# OpenBook_schematic.net
KiCad netlist of a schematic drawn in EAGLE
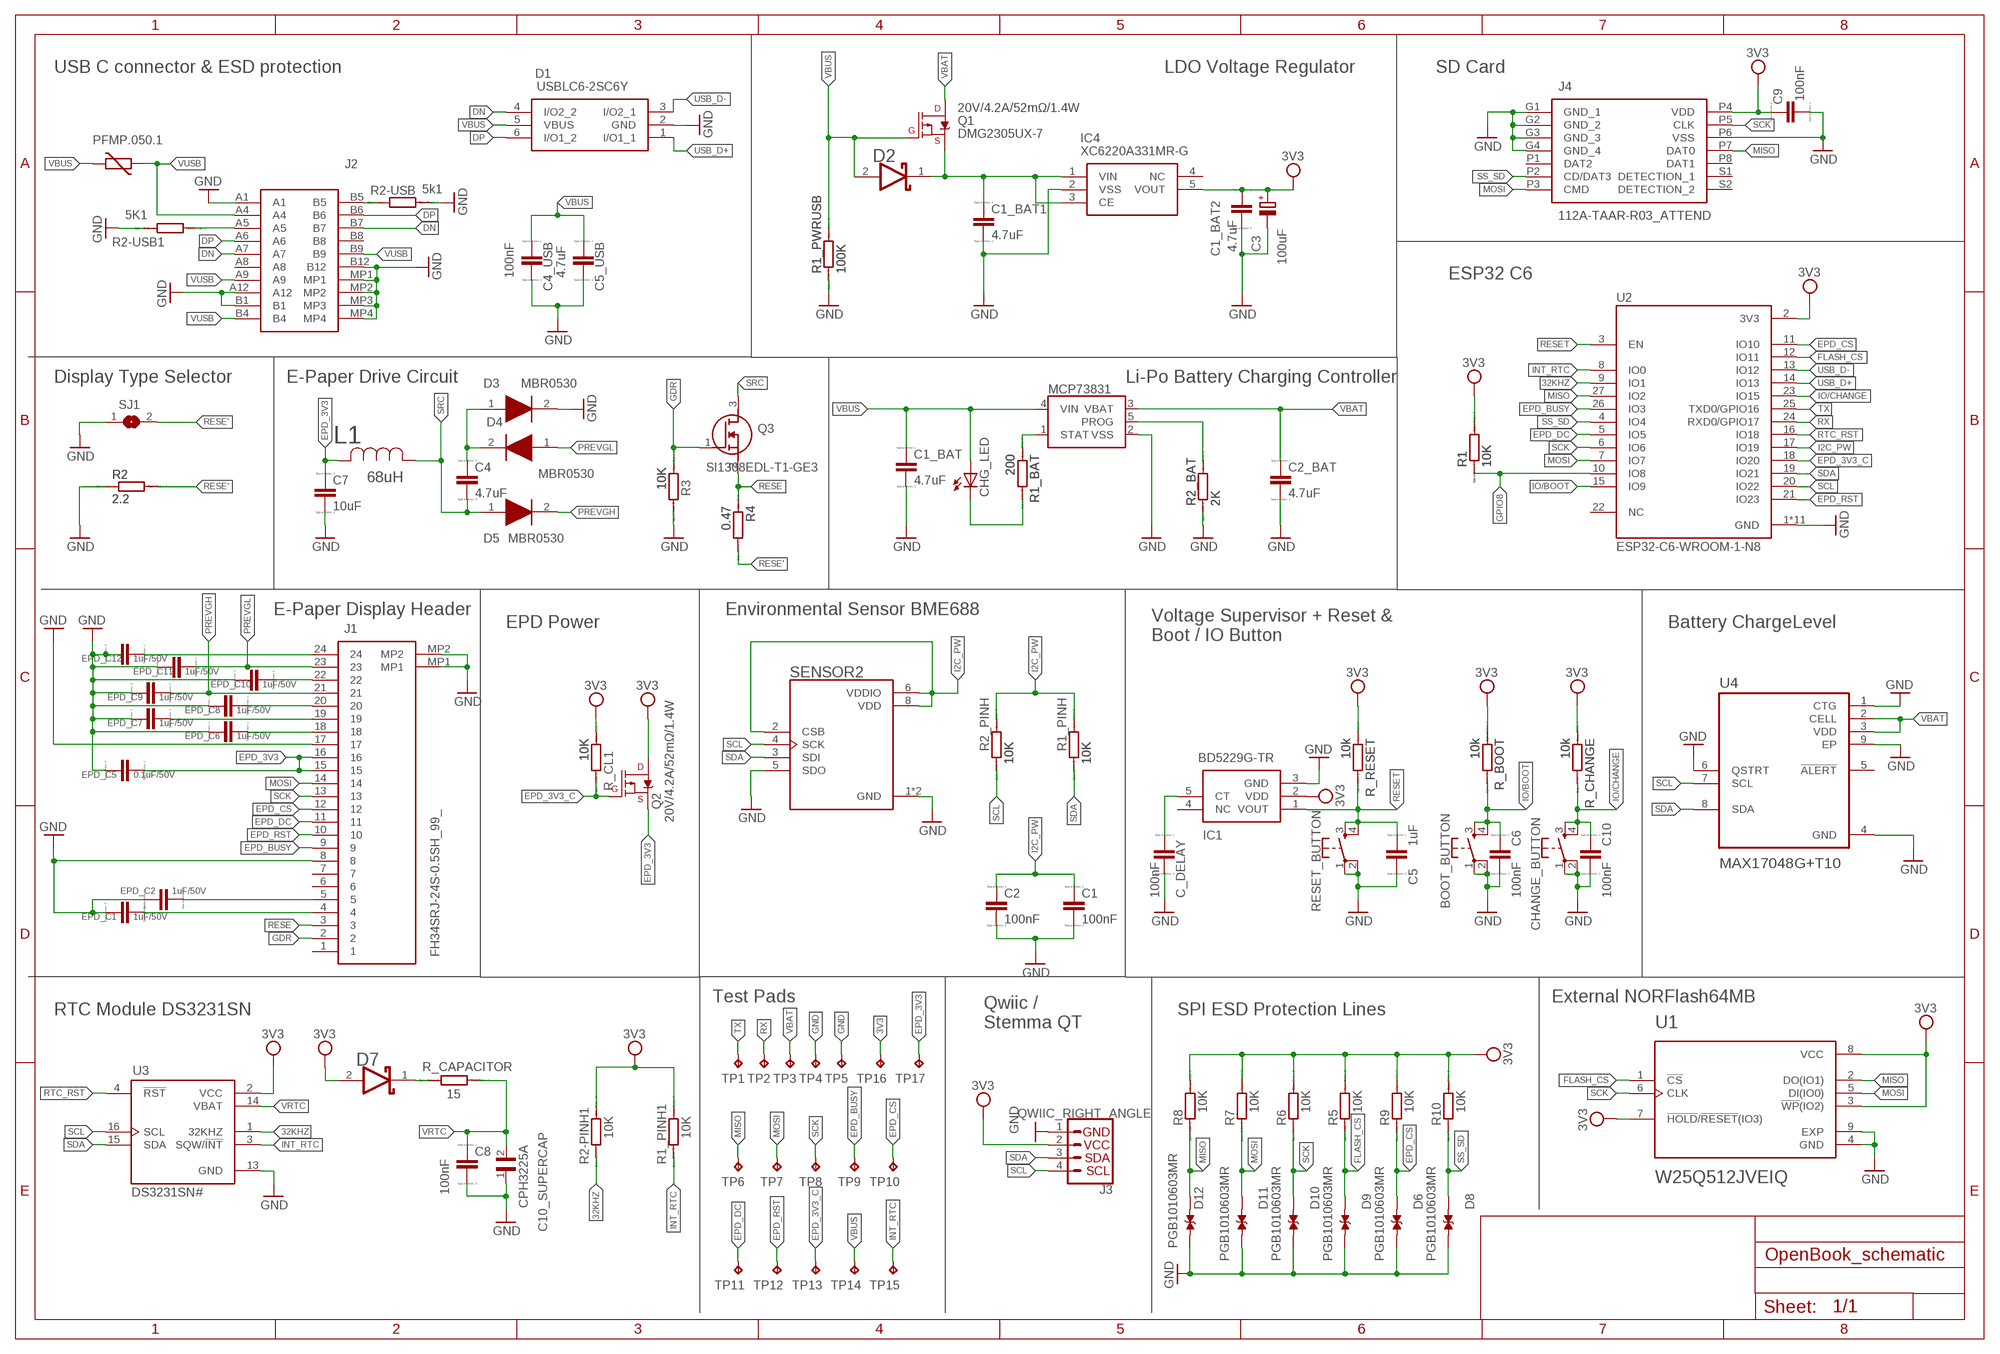
[diagram p0: schematic, sheet 1]

(export (version "E")
  (design (tool "Eeschema 10.0.6"))
  (components
    (comp (ref "BOOT_BUTTON")
      (value "BUTTON_CUSYOMV1")
      (footprint "eagle-import:MYBUTTON")
      (libsource (lib "eagle-import") (part "BUTTON_CUSYOMV1"))
    )
    (comp (ref "C1")
      (value "100nF")
      (footprint "eagle-import:EAGLE-LTSPICE_C0402")
      (libsource (lib "eagle-import") (part "EAGLE-LTSPICE_CC0402"))
    )
    (comp (ref "C1_BAT")
      (value "4.7uF")
      (footprint "eagle-import:EAGLE-LTSPICE_C0402")
      (libsource (lib "eagle-import") (part "EAGLE-LTSPICE_CC0402"))
    )
    (comp (ref "C1_BAT1")
      (value "4.7uF")
      (footprint "eagle-import:EAGLE-LTSPICE_C0402")
      (libsource (lib "eagle-import") (part "EAGLE-LTSPICE_CC0402"))
    )
    (comp (ref "C1_BAT2")
      (value "4.7uF")
      (footprint "eagle-import:EAGLE-LTSPICE_C0402")
      (libsource (lib "eagle-import") (part "EAGLE-LTSPICE_CC0402"))
    )
    (comp (ref "C2")
      (value "100nF")
      (footprint "eagle-import:EAGLE-LTSPICE_C0402")
      (libsource (lib "eagle-import") (part "EAGLE-LTSPICE_CC0402"))
    )
    (comp (ref "C2_BAT")
      (value "4.7uF")
      (footprint "eagle-import:EAGLE-LTSPICE_C0402")
      (libsource (lib "eagle-import") (part "EAGLE-LTSPICE_CC0402"))
    )
    (comp (ref "C3")
      (value "100uF")
      (footprint "eagle-import:RCL_CT3528")
      (libsource (lib "eagle-import") (part "RCL_CPOL-EUCT3528"))
    )
    (comp (ref "C4")
      (value "4.7uF")
      (footprint "eagle-import:EAGLE-LTSPICE_C0402")
      (libsource (lib "eagle-import") (part "EAGLE-LTSPICE_CC0402"))
    )
    (comp (ref "C4_USB")
      (value "100nF")
      (footprint "eagle-import:EAGLE-LTSPICE_C0402")
      (libsource (lib "eagle-import") (part "EAGLE-LTSPICE_CC0402"))
    )
    (comp (ref "C5")
      (value "1uF")
      (footprint "eagle-import:EAGLE-LTSPICE_C0402")
      (libsource (lib "eagle-import") (part "EAGLE-LTSPICE_CC0402"))
    )
    (comp (ref "C5_USB")
      (value "4.7uF")
      (footprint "eagle-import:EAGLE-LTSPICE_C0402")
      (libsource (lib "eagle-import") (part "EAGLE-LTSPICE_CC0402"))
    )
    (comp (ref "C6")
      (value "100nF")
      (footprint "eagle-import:EAGLE-LTSPICE_C0402")
      (libsource (lib "eagle-import") (part "EAGLE-LTSPICE_CC0402"))
    )
    (comp (ref "C7")
      (value "10uF")
      (footprint "eagle-import:EAGLE-LTSPICE_C0402")
      (libsource (lib "eagle-import") (part "EAGLE-LTSPICE_CC0402"))
    )
    (comp (ref "C8")
      (value "100nF")
      (footprint "eagle-import:EAGLE-LTSPICE_C0402")
      (libsource (lib "eagle-import") (part "EAGLE-LTSPICE_CC0402"))
    )
    (comp (ref "C9")
      (value "100nF")
      (footprint "eagle-import:EAGLE-LTSPICE_C0402")
      (libsource (lib "eagle-import") (part "EAGLE-LTSPICE_CC0402"))
    )
    (comp (ref "C10")
      (value "100nF")
      (footprint "eagle-import:EAGLE-LTSPICE_C0402")
      (libsource (lib "eagle-import") (part "EAGLE-LTSPICE_CC0402"))
    )
    (comp (ref "C10_SUPERCAP")
      (value "CPH3225A")
      (footprint "eagle-import:CAPCP3225X100N")
      (fields (field (name "MF") "Seiko Instruments"))
      (libsource (lib "eagle-import") (part "CPH3225A"))
    )
    (comp (ref "CHANGE_BUTTON")
      (value "BUTTON_CUSYOMV1")
      (footprint "eagle-import:MYBUTTON")
      (libsource (lib "eagle-import") (part "BUTTON_CUSYOMV1"))
    )
    (comp (ref "CHG_LED")
      (value "ADAFRUIT_LEDCHIP-LED0603")
      (footprint "eagle-import:ADAFRUIT_CHIP-LED0603")
      (libsource (lib "eagle-import") (part "ADAFRUIT_LEDCHIP-LED0603"))
    )
    (comp (ref "C_DELAY")
      (value "100nF")
      (footprint "eagle-import:EAGLE-LTSPICE_C0402")
      (libsource (lib "eagle-import") (part "EAGLE-LTSPICE_CC0402"))
    )
    (comp (ref "D1")
      (value "USBLC6-2SC6Y")
      (footprint "eagle-import:SOT95P280X145-6N")
      (fields (field (name "MF") "STMicroelectronics"))
      (libsource (lib "eagle-import") (part "USBLC6-2SC6Y"))
    )
    (comp (ref "D2")
      (value "ESP32_WROVER_AVX---SD0805S020S1R0_AVX_SD0805S020S1R0_0_0AVX_SD0805S020S1R0_0_0")
      (footprint "eagle-import:ESP32_WROVER_AVX---SD0805S020S1R0_AVX_SD0805S020S1R0_0")
      (fields
        (field (name "DIGIKEY_PART_NUMBER") "478-7800-1-ND")
        (field (name "MF") "AVX")
        (field (name "MOUSER_PART_NUMBER") "581-SD0805S020S1R0")
      )
      (libsource (lib "eagle-import") (part "ESP32_WROVER_AVX---SD0805S020S1R0_AVX_SD0805S020S1R0_0_0AVX_SD0805S020S1R0_0_0"))
    )
    (comp (ref "D3")
      (value "MBR0530")
      (footprint "eagle-import:SOD3716X135N")
      (libsource (lib "eagle-import") (part "MBR0530"))
    )
    (comp (ref "D4")
      (value "MBR0530")
      (footprint "eagle-import:SOD3716X135N")
      (libsource (lib "eagle-import") (part "MBR0530"))
    )
    (comp (ref "D5")
      (value "MBR0530")
      (footprint "eagle-import:SOD3716X135N")
      (libsource (lib "eagle-import") (part "MBR0530"))
    )
    (comp (ref "D6")
      (value "PGB1010603MR")
      (footprint "eagle-import:DIOC1608X36N")
      (libsource (lib "eagle-import") (part "PGB1010603MR"))
    )
    (comp (ref "D7")
      (value "ESP32_WROVER_AVX---SD0805S020S1R0_AVX_SD0805S020S1R0_0_0AVX_SD0805S020S1R0_0_0")
      (footprint "eagle-import:ESP32_WROVER_AVX---SD0805S020S1R0_AVX_SD0805S020S1R0_0")
      (fields
        (field (name "DIGIKEY_PART_NUMBER") "478-7800-1-ND")
        (field (name "MF") "AVX")
        (field (name "MOUSER_PART_NUMBER") "581-SD0805S020S1R0")
      )
      (libsource (lib "eagle-import") (part "ESP32_WROVER_AVX---SD0805S020S1R0_AVX_SD0805S020S1R0_0_0AVX_SD0805S020S1R0_0_0"))
    )
    (comp (ref "D8")
      (value "PGB1010603MR")
      (footprint "eagle-import:DIOC1608X36N")
      (libsource (lib "eagle-import") (part "PGB1010603MR"))
    )
    (comp (ref "D9")
      (value "PGB1010603MR")
      (footprint "eagle-import:DIOC1608X36N")
      (libsource (lib "eagle-import") (part "PGB1010603MR"))
    )
    (comp (ref "D10")
      (value "PGB1010603MR")
      (footprint "eagle-import:DIOC1608X36N")
      (libsource (lib "eagle-import") (part "PGB1010603MR"))
    )
    (comp (ref "D11")
      (value "PGB1010603MR")
      (footprint "eagle-import:DIOC1608X36N")
      (libsource (lib "eagle-import") (part "PGB1010603MR"))
    )
    (comp (ref "D12")
      (value "PGB1010603MR")
      (footprint "eagle-import:DIOC1608X36N")
      (libsource (lib "eagle-import") (part "PGB1010603MR"))
    )
    (comp (ref "EPD_C1")
      (value "1uF/50V")
      (footprint "eagle-import:EAGLE-LTSPICE_C0402")
      (libsource (lib "eagle-import") (part "EAGLE-LTSPICE_CC0402"))
    )
    (comp (ref "EPD_C2")
      (value "1uF/50V")
      (footprint "eagle-import:EAGLE-LTSPICE_C0402")
      (libsource (lib "eagle-import") (part "EAGLE-LTSPICE_CC0402"))
    )
    (comp (ref "EPD_C5")
      (value "0.1uF/50V")
      (footprint "eagle-import:EAGLE-LTSPICE_C0402")
      (libsource (lib "eagle-import") (part "EAGLE-LTSPICE_CC0402"))
    )
    (comp (ref "EPD_C6")
      (value "1uF/50V")
      (footprint "eagle-import:EAGLE-LTSPICE_C0402")
      (libsource (lib "eagle-import") (part "EAGLE-LTSPICE_CC0402"))
    )
    (comp (ref "EPD_C7")
      (value "1uF/50V")
      (footprint "eagle-import:EAGLE-LTSPICE_C0402")
      (libsource (lib "eagle-import") (part "EAGLE-LTSPICE_CC0402"))
    )
    (comp (ref "EPD_C8")
      (value "1uF/50V")
      (footprint "eagle-import:EAGLE-LTSPICE_C0402")
      (libsource (lib "eagle-import") (part "EAGLE-LTSPICE_CC0402"))
    )
    (comp (ref "EPD_C9")
      (value "1uF/50V")
      (footprint "eagle-import:EAGLE-LTSPICE_C0402")
      (libsource (lib "eagle-import") (part "EAGLE-LTSPICE_CC0402"))
    )
    (comp (ref "EPD_C10")
      (value "1uF/50V")
      (footprint "eagle-import:EAGLE-LTSPICE_C0402")
      (libsource (lib "eagle-import") (part "EAGLE-LTSPICE_CC0402"))
    )
    (comp (ref "EPD_C11")
      (value "1uF/50V")
      (footprint "eagle-import:EAGLE-LTSPICE_C0402")
      (libsource (lib "eagle-import") (part "EAGLE-LTSPICE_CC0402"))
    )
    (comp (ref "EPD_C12")
      (value "1uF/50V")
      (footprint "eagle-import:EAGLE-LTSPICE_C0402")
      (libsource (lib "eagle-import") (part "EAGLE-LTSPICE_CC0402"))
    )
    (comp (ref "IC1")
      (value "BD5229G-TR")
      (footprint "eagle-import:SOT95P280X125-5N")
      (fields (field (name "MOUSER_PART_NUMBER") "755-BD5229G-TR"))
      (libsource (lib "eagle-import") (part "BD5229G-TR"))
    )
    (comp (ref "IC4")
      (value "XC6220A331MR-G")
      (footprint "eagle-import:SOT95P280X120-5N")
      (fields (field (name "MOUSER_PART_NUMBER") "865-XC6220A331MR-G"))
      (libsource (lib "eagle-import") (part "XC6220A331MR-G"))
    )
    (comp (ref "J1")
      (value "FH34SRJ-24S-0.5SH_99_")
      (footprint "eagle-import:FH34SRJ24S05SH99")
      (fields
        (field (name "MANUFACTURER_PART_NUMBER") "FH34SRJ-24S-0.5SH(99)")
        (field (name "MOUSER_PART_NUMBER") "798-FH34SRJ24S05SH99")
      )
      (libsource (lib "eagle-import") (part "FH34SRJ-24S-0.5SH_99_"))
    )
    (comp (ref "J2")
      (value "SAMACSYS_PARTS_USB4110-GF-A")
      (footprint "eagle-import:SAMACSYS_PARTS_USB4110GFA")
      (fields
        (field (name "MANUFACTURER_PART_NUMBER") "USB4110-GF-A")
        (field (name "MOUSER_PART_NUMBER") "640-USB4110-GF-A")
      )
      (libsource (lib "eagle-import") (part "SAMACSYS_PARTS_USB4110-GF-A"))
    )
    (comp (ref "J3")
      (value "QWIIC_RIGHT_ANGLE")
      (footprint "eagle-import:JST04_1MM_RA")
      (libsource (lib "eagle-import") (part "QWIIC_CONNECTORJS-1MM"))
    )
    (comp (ref "J4")
      (value "112A-TAAR-R03_ATTEND")
      (footprint "eagle-import:112ATAARR03ATTEND")
      (fields (field (name "MANUFACTURER_PART_NUMBER") "112A-TAAR-R03 ATTEND"))
      (libsource (lib "eagle-import") (part "112A-TAAR-R03_ATTEND"))
    )
    (comp (ref "L1")
      (value "68uH")
      (footprint "eagle-import:IND_4828-WE-TPC_WRE")
      (fields
        (field (name "MANUFACTURER_PART_NUMBER") "744043680")
        (field (name "COPYRIGHT") "Copyright (C) 2024 Ultra Librarian. All rights reserved.")
      )
      (libsource (lib "eagle-import") (part "744043680IND_4828-WE-TPC_WRE"))
    )
    (comp (ref "MCP73831")
      (value "ESP32_WROVER_SPARKFUN-IC-POWER_MCP73831")
      (footprint "eagle-import:ESP32_WROVER_SPARKFUN-IC-POWER_SOT23-5")
      (libsource (lib "eagle-import") (part "ESP32_WROVER_SPARKFUN-IC-POWER_MCP73831"))
    )
    (comp (ref "PFMP.050.1")
      (value "ESP32C6_VARISTORCN1812")
      (footprint "eagle-import:ESP32C6_VARISTOR_CT_CN1812")
      (libsource (lib "eagle-import") (part "ESP32C6_VARISTORCN1812"))
    )
    (comp (ref "Q1")
      (value "20V/4.2A/52mΩ/1.4W")
      (footprint "eagle-import:ESP32_WROVER_SPARKFUN-DISCRETESEMI_SOT23-3")
      (libsource (lib "eagle-import") (part "ESP32_WROVER_SPARKFUN-DISCRETESEMI_MOSFET_PCH-DMG2305UX-7"))
    )
    (comp (ref "Q2")
      (value "20V/4.2A/52mΩ/1.4W")
      (footprint "eagle-import:ESP32_WROVER_SPARKFUN-DISCRETESEMI_SOT23-3")
      (libsource (lib "eagle-import") (part "ESP32_WROVER_SPARKFUN-DISCRETESEMI_MOSFET_PCH-DMG2305UX-7"))
    )
    (comp (ref "Q3")
      (value "SI1308EDL-T1-GE3")
      (footprint "eagle-import:SOT65P210X110-3N")
      (fields (field (name "MF") "Vishay Siliconix"))
      (libsource (lib "eagle-import") (part "SI1308EDL-T1-GE3"))
    )
    (comp (ref "R1")
      (value "10K")
      (footprint "eagle-import:ESP32_WROVER_EAGLE-LTSPICE_R0402")
      (libsource (lib "eagle-import") (part "ESP32_WROVER_EAGLE-LTSPICE_RR0402"))
    )
    (comp (ref "R1_BAT")
      (value "200")
      (footprint "eagle-import:ESP32_WROVER_EAGLE-LTSPICE_R0402")
      (libsource (lib "eagle-import") (part "ESP32_WROVER_EAGLE-LTSPICE_RR0402"))
    )
    (comp (ref "R1_PINH")
      (value "10K")
      (footprint "eagle-import:ESP32_WROVER_EAGLE-LTSPICE_R0402")
      (libsource (lib "eagle-import") (part "ESP32_WROVER_EAGLE-LTSPICE_RR0402"))
    )
    (comp (ref "R1_PINH1")
      (value "10K")
      (footprint "eagle-import:ESP32_WROVER_EAGLE-LTSPICE_R0402")
      (libsource (lib "eagle-import") (part "ESP32_WROVER_EAGLE-LTSPICE_RR0402"))
    )
    (comp (ref "R1_PWRUSB")
      (value "100K")
      (footprint "eagle-import:ESP32_WROVER_EAGLE-LTSPICE_R0402")
      (libsource (lib "eagle-import") (part "ESP32_WROVER_EAGLE-LTSPICE_RR0402"))
    )
    (comp (ref "R2")
      (value "2.2")
      (footprint "eagle-import:ESP32_WROVER_EAGLE-LTSPICE_R0402")
      (libsource (lib "eagle-import") (part "ESP32_WROVER_EAGLE-LTSPICE_RR0402"))
    )
    (comp (ref "R2-PINH1")
      (value "10K")
      (footprint "eagle-import:ESP32_WROVER_EAGLE-LTSPICE_R0402")
      (libsource (lib "eagle-import") (part "ESP32_WROVER_EAGLE-LTSPICE_RR0402"))
    )
    (comp (ref "R2-USB")
      (value "5k1")
      (footprint "eagle-import:ESP32_WROVER_EAGLE-LTSPICE_R0402")
      (libsource (lib "eagle-import") (part "ESP32_WROVER_EAGLE-LTSPICE_RR0402"))
    )
    (comp (ref "R2-USB1")
      (value "5K1")
      (footprint "eagle-import:ESP32_WROVER_EAGLE-LTSPICE_R0402")
      (libsource (lib "eagle-import") (part "ESP32_WROVER_EAGLE-LTSPICE_RR0402"))
    )
    (comp (ref "R2_BAT")
      (value "2K")
      (footprint "eagle-import:ESP32_WROVER_EAGLE-LTSPICE_R0402")
      (libsource (lib "eagle-import") (part "ESP32_WROVER_EAGLE-LTSPICE_RR0402"))
    )
    (comp (ref "R2_PINH")
      (value "10K")
      (footprint "eagle-import:ESP32_WROVER_EAGLE-LTSPICE_R0402")
      (libsource (lib "eagle-import") (part "ESP32_WROVER_EAGLE-LTSPICE_RR0402"))
    )
    (comp (ref "R3")
      (value "10K")
      (footprint "eagle-import:ESP32_WROVER_EAGLE-LTSPICE_R0402")
      (libsource (lib "eagle-import") (part "ESP32_WROVER_EAGLE-LTSPICE_RR0402"))
    )
    (comp (ref "R4")
      (value "0.47")
      (footprint "eagle-import:ESP32_WROVER_EAGLE-LTSPICE_R0402")
      (libsource (lib "eagle-import") (part "ESP32_WROVER_EAGLE-LTSPICE_RR0402"))
    )
    (comp (ref "R5")
      (value "10K")
      (footprint "eagle-import:ESP32_WROVER_EAGLE-LTSPICE_R0402")
      (libsource (lib "eagle-import") (part "ESP32_WROVER_EAGLE-LTSPICE_RR0402"))
    )
    (comp (ref "R6")
      (value "10K")
      (footprint "eagle-import:ESP32_WROVER_EAGLE-LTSPICE_R0402")
      (libsource (lib "eagle-import") (part "ESP32_WROVER_EAGLE-LTSPICE_RR0402"))
    )
    (comp (ref "R7")
      (value "10K")
      (footprint "eagle-import:ESP32_WROVER_EAGLE-LTSPICE_R0402")
      (libsource (lib "eagle-import") (part "ESP32_WROVER_EAGLE-LTSPICE_RR0402"))
    )
    (comp (ref "R8")
      (value "10K")
      (footprint "eagle-import:ESP32_WROVER_EAGLE-LTSPICE_R0402")
      (libsource (lib "eagle-import") (part "ESP32_WROVER_EAGLE-LTSPICE_RR0402"))
    )
    (comp (ref "R9")
      (value "10K")
      (footprint "eagle-import:ESP32_WROVER_EAGLE-LTSPICE_R0402")
      (libsource (lib "eagle-import") (part "ESP32_WROVER_EAGLE-LTSPICE_RR0402"))
    )
    (comp (ref "R10")
      (value "10K")
      (footprint "eagle-import:ESP32_WROVER_EAGLE-LTSPICE_R0402")
      (libsource (lib "eagle-import") (part "ESP32_WROVER_EAGLE-LTSPICE_RR0402"))
    )
    (comp (ref "RESET_BUTTON")
      (value "BUTTON_CUSYOMV1")
      (footprint "eagle-import:MYBUTTON")
      (libsource (lib "eagle-import") (part "BUTTON_CUSYOMV1"))
    )
    (comp (ref "R_BOOT")
      (value "10k")
      (footprint "eagle-import:ESP32_WROVER_EAGLE-LTSPICE_R0402")
      (libsource (lib "eagle-import") (part "ESP32_WROVER_EAGLE-LTSPICE_RR0402"))
    )
    (comp (ref "R_CAPACITOR")
      (value "15")
      (footprint "eagle-import:ESP32_WROVER_EAGLE-LTSPICE_R0402")
      (libsource (lib "eagle-import") (part "ESP32_WROVER_EAGLE-LTSPICE_RR0402"))
    )
    (comp (ref "R_CHANGE")
      (value "10k")
      (footprint "eagle-import:ESP32_WROVER_EAGLE-LTSPICE_R0402")
      (libsource (lib "eagle-import") (part "ESP32_WROVER_EAGLE-LTSPICE_RR0402"))
    )
    (comp (ref "R_CL1")
      (value "10K")
      (footprint "eagle-import:ESP32_WROVER_EAGLE-LTSPICE_R0402")
      (libsource (lib "eagle-import") (part "ESP32_WROVER_EAGLE-LTSPICE_RR0402"))
    )
    (comp (ref "R_RESET")
      (value "10k")
      (footprint "eagle-import:ESP32_WROVER_EAGLE-LTSPICE_R0402")
      (libsource (lib "eagle-import") (part "ESP32_WROVER_EAGLE-LTSPICE_RR0402"))
    )
    (comp (ref "SENSOR2")
      (value "ESP32_WROVER_BME680_BME680")
      (footprint "eagle-import:ESP32_WROVER_BME680_PSON80P300X300X100-8N")
      (fields (field (name "MF") "Bosch Sensortec") (field (name "MP") "BME680"))
      (libsource (lib "eagle-import") (part "ESP32_WROVER_BME680_BME680"))
    )
    (comp (ref "SJ1") (value "SJ") (footprint "eagle-import:SJ") (libsource (lib "eagle-import") (part "SJ")))
    (comp (ref "TP1")
      (value "TPTP20R")
      (footprint "eagle-import:TP20R")
      (libsource (lib "eagle-import") (part "TPTP20R"))
    )
    (comp (ref "TP2")
      (value "TPTP20R")
      (footprint "eagle-import:TP20R")
      (libsource (lib "eagle-import") (part "TPTP20R"))
    )
    (comp (ref "TP3")
      (value "TPTP20R")
      (footprint "eagle-import:TP20R")
      (libsource (lib "eagle-import") (part "TPTP20R"))
    )
    (comp (ref "TP4")
      (value "TPTP20R")
      (footprint "eagle-import:TP20R")
      (libsource (lib "eagle-import") (part "TPTP20R"))
    )
    (comp (ref "TP5")
      (value "TPTP20R")
      (footprint "eagle-import:TP20R")
      (libsource (lib "eagle-import") (part "TPTP20R"))
    )
    (comp (ref "TP6")
      (value "TPTP20R")
      (footprint "eagle-import:TP20R")
      (libsource (lib "eagle-import") (part "TPTP20R"))
    )
    (comp (ref "TP7")
      (value "TPTP20R")
      (footprint "eagle-import:TP20R")
      (libsource (lib "eagle-import") (part "TPTP20R"))
    )
    (comp (ref "TP8")
      (value "TPTP20R")
      (footprint "eagle-import:TP20R")
      (libsource (lib "eagle-import") (part "TPTP20R"))
    )
    (comp (ref "TP9")
      (value "TPTP20R")
      (footprint "eagle-import:TP20R")
      (libsource (lib "eagle-import") (part "TPTP20R"))
    )
    (comp (ref "TP10")
      (value "TPTP20R")
      (footprint "eagle-import:TP20R")
      (libsource (lib "eagle-import") (part "TPTP20R"))
    )
    (comp (ref "TP11")
      (value "TPTP20R")
      (footprint "eagle-import:TP20R")
      (libsource (lib "eagle-import") (part "TPTP20R"))
    )
    (comp (ref "TP12")
      (value "TPTP20R")
      (footprint "eagle-import:TP20R")
      (libsource (lib "eagle-import") (part "TPTP20R"))
    )
    (comp (ref "TP13")
      (value "TPTP20R")
      (footprint "eagle-import:TP20R")
      (libsource (lib "eagle-import") (part "TPTP20R"))
    )
    (comp (ref "TP14")
      (value "TPTP20R")
      (footprint "eagle-import:TP20R")
      (libsource (lib "eagle-import") (part "TPTP20R"))
    )
    (comp (ref "TP15")
      (value "TPTP20R")
      (footprint "eagle-import:TP20R")
      (libsource (lib "eagle-import") (part "TPTP20R"))
    )
    (comp (ref "TP16")
      (value "TPTP20R")
      (footprint "eagle-import:TP20R")
      (libsource (lib "eagle-import") (part "TPTP20R"))
    )
    (comp (ref "TP17")
      (value "TPTP20R")
      (footprint "eagle-import:TP20R")
      (libsource (lib "eagle-import") (part "TPTP20R"))
    )
    (comp (ref "U1")
      (value "W25Q512JVEIQ")
      (footprint "eagle-import:SON127P600X800X80-9N")
      (fields (field (name "MF") "Winbond Electronics"))
      (libsource (lib "eagle-import") (part "W25Q512JVEIQ"))
    )
    (comp (ref "U2")
      (value "ESP32-C6-WROOM-1-N8")
      (footprint "eagle-import:XCVR_ESP32-C6-WROOM-1-N8")
      (fields (field (name "MF") "Espressif Systems"))
      (libsource (lib "eagle-import") (part "ESP32-C6-WROOM-1-N8"))
    )
    (comp (ref "U3")
      (value "DS3231SN#")
      (footprint "eagle-import:SOIC127P1032X265-16N")
      (fields (field (name "MF") "Analog Devices"))
      (libsource (lib "eagle-import") (part "DS3231SN#"))
    )
    (comp (ref "U4")
      (value "MAX17048G+T10")
      (footprint "eagle-import:SON50P200X200X80-9N")
      (fields (field (name "MF") "Analog Devices"))
      (libsource (lib "eagle-import") (part "MAX17048G+T10"))
    )
  )
  (nets
    (net (code "1") (name "3V3") (class "Default")
      (node (ref "C1_BAT2") (pin "1") (pinfunction "1_1") (pintype "passive"))
      (node (ref "C3") (pin "+") (pinfunction "+_+") (pintype "passive"))
      (node (ref "C9") (pin "1") (pinfunction "1_1") (pintype "passive"))
      (node (ref "D7") (pin "2") (pinfunction "ANODE_2") (pintype "bidirectional"))
      (node (ref "IC1") (pin "2") (pinfunction "VDD_2") (pintype "bidirectional"))
      (node (ref "IC4") (pin "5") (pinfunction "VOUT_5") (pintype "bidirectional"))
      (node (ref "J3") (pin "2") (pinfunction "2_2") (pintype "power_in"))
      (node (ref "J4") (pin "P4") (pinfunction "VDD_P4") (pintype "bidirectional"))
      (node (ref "Q2") (pin "3") (pinfunction "D_3") (pintype "bidirectional"))
      (node (ref "R1") (pin "2") (pinfunction "2_2") (pintype "passive"))
      (node (ref "R10") (pin "2") (pinfunction "2_2") (pintype "passive"))
      (node (ref "R1_PINH1") (pin "2") (pinfunction "2_2") (pintype "passive"))
      (node (ref "R2-PINH1") (pin "2") (pinfunction "2_2") (pintype "passive"))
      (node (ref "R5") (pin "2") (pinfunction "2_2") (pintype "passive"))
      (node (ref "R6") (pin "2") (pinfunction "2_2") (pintype "passive"))
      (node (ref "R7") (pin "2") (pinfunction "2_2") (pintype "passive"))
      (node (ref "R8") (pin "2") (pinfunction "2_2") (pintype "passive"))
      (node (ref "R9") (pin "2") (pinfunction "2_2") (pintype "passive"))
      (node (ref "R_BOOT") (pin "1") (pinfunction "1_1") (pintype "passive"))
      (node (ref "R_CHANGE") (pin "1") (pinfunction "1_1") (pintype "passive"))
      (node (ref "R_CL1") (pin "1") (pinfunction "1_1") (pintype "passive"))
      (node (ref "R_RESET") (pin "1") (pinfunction "1_1") (pintype "passive"))
      (node (ref "TP16") (pin "TP") (pinfunction "TP_TP") (pintype "input"))
      (node (ref "U1") (pin "3") (pinfunction "~{WP}(IO2)_3") (pintype "bidirectional"))
      (node (ref "U1") (pin "7") (pinfunction "~{HOLD}/~{RESET}(IO3)_7") (pintype "bidirectional"))
      (node (ref "U1") (pin "8") (pinfunction "VCC_8") (pintype "power_in"))
      (node (ref "U2") (pin "2") (pinfunction "3V3_2") (pintype "power_in"))
      (node (ref "U3") (pin "2") (pinfunction "VCC_2") (pintype "power_in"))
    )
    (net (code "2") (name "32KHZ") (class "Default")
      (node (ref "R2-PINH1") (pin "1") (pinfunction "1_1") (pintype "passive"))
      (node (ref "U2") (pin "9") (pinfunction "IO1_9") (pintype "bidirectional"))
      (node (ref "U3") (pin "1") (pinfunction "32KHZ_1") (pintype "output"))
    )
    (net (code "3") (name "DN") (class "Default")
      (node (ref "D1") (pin "4") (pinfunction "I/O2_2_4") (pintype "bidirectional"))
      (node (ref "J2") (pin "A7") (pinfunction "A7_A7") (pintype "bidirectional"))
      (node (ref "J2") (pin "B7") (pinfunction "B7_B7") (pintype "bidirectional"))
    )
    (net (code "4") (name "DP") (class "Default")
      (node (ref "D1") (pin "6") (pinfunction "I/O1_2_6") (pintype "bidirectional"))
      (node (ref "J2") (pin "A6") (pinfunction "A6_A6") (pintype "bidirectional"))
      (node (ref "J2") (pin "B6") (pinfunction "B6_B6") (pintype "bidirectional"))
    )
    (net (code "5") (name "EPD_3V3") (class "Default")
      (node (ref "C7") (pin "1") (pinfunction "1_1") (pintype "passive"))
      (node (ref "EPD_C5") (pin "1") (pinfunction "1_1") (pintype "passive"))
      (node (ref "J1") (pin "15") (pinfunction "15_15") (pintype "bidirectional"))
      (node (ref "J1") (pin "16") (pinfunction "16_16") (pintype "bidirectional"))
      (node (ref "L1") (pin "2") (pinfunction "2_2") (pintype "passive"))
      (node (ref "Q2") (pin "2") (pinfunction "S_2") (pintype "bidirectional"))
      (node (ref "TP17") (pin "TP") (pinfunction "TP_TP") (pintype "input"))
    )
    (net (code "6") (name "EPD_3V3_C") (class "Default")
      (node (ref "Q2") (pin "1") (pinfunction "G_1") (pintype "bidirectional"))
      (node (ref "R_CL1") (pin "2") (pinfunction "2_2") (pintype "passive"))
      (node (ref "TP13") (pin "TP") (pinfunction "TP_TP") (pintype "input"))
      (node (ref "U2") (pin "18") (pinfunction "IO20_18") (pintype "bidirectional"))
    )
    (net (code "7") (name "EPD_BUSY") (class "Default")
      (node (ref "J1") (pin "9") (pinfunction "9_9") (pintype "bidirectional"))
      (node (ref "TP9") (pin "TP") (pinfunction "TP_TP") (pintype "input"))
      (node (ref "U2") (pin "26") (pinfunction "IO3_26") (pintype "bidirectional"))
    )
    (net (code "8") (name "EPD_CS") (class "Default")
      (node (ref "D6") (pin "2") (pinfunction "2_2") (pintype "passive"))
      (node (ref "J1") (pin "12") (pinfunction "12_12") (pintype "bidirectional"))
      (node (ref "R9") (pin "1") (pinfunction "1_1") (pintype "passive"))
      (node (ref "TP10") (pin "TP") (pinfunction "TP_TP") (pintype "input"))
      (node (ref "U2") (pin "11") (pinfunction "IO10_11") (pintype "bidirectional"))
    )
    (net (code "9") (name "EPD_DC") (class "Default")
      (node (ref "J1") (pin "11") (pinfunction "11_11") (pintype "bidirectional"))
      (node (ref "TP11") (pin "TP") (pinfunction "TP_TP") (pintype "input"))
      (node (ref "U2") (pin "5") (pinfunction "IO5_5") (pintype "bidirectional"))
    )
    (net (code "10") (name "EPD_RST") (class "Default")
      (node (ref "J1") (pin "10") (pinfunction "10_10") (pintype "bidirectional"))
      (node (ref "TP12") (pin "TP") (pinfunction "TP_TP") (pintype "input"))
      (node (ref "U2") (pin "21") (pinfunction "IO23_21") (pintype "bidirectional"))
    )
    (net (code "11") (name "FLASH_CS") (class "Default")
      (node (ref "D9") (pin "2") (pinfunction "2_2") (pintype "passive"))
      (node (ref "R5") (pin "1") (pinfunction "1_1") (pintype "passive"))
      (node (ref "U1") (pin "1") (pinfunction "~{CS}_1") (pintype "input"))
      (node (ref "U2") (pin "12") (pinfunction "IO11_12") (pintype "bidirectional"))
    )
    (net (code "12") (name "GDR") (class "Default")
      (node (ref "J1") (pin "2") (pinfunction "2_2") (pintype "bidirectional"))
      (node (ref "Q3") (pin "1") (pinfunction "G_1") (pintype "bidirectional"))
      (node (ref "R3") (pin "1") (pinfunction "1_1") (pintype "passive"))
    )
    (net (code "13") (name "GND") (class "Default")
      (node (ref "BOOT_BUTTON") (pin "1") (pinfunction "1_1") (pintype "passive"))
      (node (ref "BOOT_BUTTON") (pin "2") (pinfunction "2_2") (pintype "passive"))
      (node (ref "C1") (pin "2") (pinfunction "2_2") (pintype "passive"))
      (node (ref "C10") (pin "2") (pinfunction "2_2") (pintype "passive"))
      (node (ref "C10_SUPERCAP") (pin "1") (pinfunction "1_1") (pintype "passive"))
      (node (ref "C1_BAT") (pin "2") (pinfunction "2_2") (pintype "passive"))
      (node (ref "C1_BAT1") (pin "2") (pinfunction "2_2") (pintype "passive"))
      (node (ref "C1_BAT2") (pin "2") (pinfunction "2_2") (pintype "passive"))
      (node (ref "C2") (pin "2") (pinfunction "2_2") (pintype "passive"))
      (node (ref "C2_BAT") (pin "2") (pinfunction "2_2") (pintype "passive"))
      (node (ref "C3") (pin "-") (pinfunction "-_-") (pintype "passive"))
      (node (ref "C4_USB") (pin "2") (pinfunction "2_2") (pintype "passive"))
      (node (ref "C5") (pin "2") (pinfunction "2_2") (pintype "passive"))
      (node (ref "C5_USB") (pin "2") (pinfunction "2_2") (pintype "passive"))
      (node (ref "C6") (pin "2") (pinfunction "2_2") (pintype "passive"))
      (node (ref "C7") (pin "2") (pinfunction "2_2") (pintype "passive"))
      (node (ref "C8") (pin "2") (pinfunction "2_2") (pintype "passive"))
      (node (ref "C9") (pin "2") (pinfunction "2_2") (pintype "passive"))
      (node (ref "CHANGE_BUTTON") (pin "1") (pinfunction "1_1") (pintype "passive"))
      (node (ref "CHANGE_BUTTON") (pin "2") (pinfunction "2_2") (pintype "passive"))
      (node (ref "C_DELAY") (pin "2") (pinfunction "2_2") (pintype "passive"))
      (node (ref "D1") (pin "2") (pinfunction "GND_2") (pintype "bidirectional"))
      (node (ref "D10") (pin "1") (pinfunction "1_1") (pintype "passive"))
      (node (ref "D11") (pin "1") (pinfunction "1_1") (pintype "passive"))
      (node (ref "D12") (pin "1") (pinfunction "1_1") (pintype "passive"))
      (node (ref "D3") (pin "2") (pinfunction "K_2") (pintype "bidirectional"))
      (node (ref "D6") (pin "1") (pinfunction "1_1") (pintype "passive"))
      (node (ref "D8") (pin "1") (pinfunction "1_1") (pintype "passive"))
      (node (ref "D9") (pin "1") (pinfunction "1_1") (pintype "passive"))
      (node (ref "EPD_C1") (pin "2") (pinfunction "2_2") (pintype "passive"))
      (node (ref "EPD_C10") (pin "2") (pinfunction "2_2") (pintype "passive"))
      (node (ref "EPD_C11") (pin "2") (pinfunction "2_2") (pintype "passive"))
      (node (ref "EPD_C12") (pin "2") (pinfunction "2_2") (pintype "passive"))
      (node (ref "EPD_C2") (pin "2") (pinfunction "2_2") (pintype "passive"))
      (node (ref "EPD_C5") (pin "2") (pinfunction "2_2") (pintype "passive"))
      (node (ref "EPD_C6") (pin "2") (pinfunction "2_2") (pintype "passive"))
      (node (ref "EPD_C7") (pin "2") (pinfunction "2_2") (pintype "passive"))
      (node (ref "EPD_C8") (pin "2") (pinfunction "2_2") (pintype "passive"))
      (node (ref "EPD_C9") (pin "2") (pinfunction "2_2") (pintype "passive"))
      (node (ref "IC1") (pin "3") (pinfunction "GND_3") (pintype "bidirectional"))
      (node (ref "IC4") (pin "2") (pinfunction "VSS_2") (pintype "bidirectional"))
      (node (ref "J1") (pin "17") (pinfunction "17_17") (pintype "bidirectional"))
      (node (ref "J1") (pin "8") (pinfunction "8_8") (pintype "bidirectional"))
      (node (ref "J1") (pin "MP1") (pinfunction "MP1_MP1") (pintype "bidirectional"))
      (node (ref "J1") (pin "MP2") (pinfunction "MP2_MP2") (pintype "bidirectional"))
      (node (ref "J2") (pin "A1") (pinfunction "A1_A1") (pintype "bidirectional"))
      (node (ref "J2") (pin "A12") (pinfunction "A12_A12") (pintype "bidirectional"))
      (node (ref "J2") (pin "B1") (pinfunction "B1_B1") (pintype "bidirectional"))
      (node (ref "J2") (pin "B12") (pinfunction "B12_B12") (pintype "bidirectional"))
      (node (ref "J2") (pin "MP1") (pinfunction "MP1_MP1") (pintype "bidirectional"))
      (node (ref "J2") (pin "MP2") (pinfunction "MP2_MP2") (pintype "bidirectional"))
      (node (ref "J2") (pin "MP3") (pinfunction "MP3_MP3") (pintype "bidirectional"))
      (node (ref "J2") (pin "MP4") (pinfunction "MP4_MP4") (pintype "bidirectional"))
      (node (ref "J3") (pin "1") (pinfunction "1_1") (pintype "power_in"))
      (node (ref "J4") (pin "G1") (pinfunction "GND_1_G1") (pintype "bidirectional"))
      (node (ref "J4") (pin "G2") (pinfunction "GND_2_G2") (pintype "bidirectional"))
      (node (ref "J4") (pin "G3") (pinfunction "GND_3_G3") (pintype "bidirectional"))
      (node (ref "J4") (pin "G4") (pinfunction "GND_4_G4") (pintype "bidirectional"))
      (node (ref "J4") (pin "P6") (pinfunction "VSS_P6") (pintype "bidirectional"))
      (node (ref "MCP73831") (pin "2") (pinfunction "VSS_2") (pintype "power_in"))
      (node (ref "R1_PWRUSB") (pin "1") (pinfunction "1_1") (pintype "passive"))
      (node (ref "R2") (pin "1") (pinfunction "1_1") (pintype "passive"))
      (node (ref "R2-USB") (pin "2") (pinfunction "2_2") (pintype "passive"))
      (node (ref "R2-USB1") (pin "1") (pinfunction "1_1") (pintype "passive"))
      (node (ref "R2_BAT") (pin "1") (pinfunction "1_1") (pintype "passive"))
      (node (ref "R3") (pin "2") (pinfunction "2_2") (pintype "passive"))
      (node (ref "RESET_BUTTON") (pin "1") (pinfunction "1_1") (pintype "passive"))
      (node (ref "RESET_BUTTON") (pin "2") (pinfunction "2_2") (pintype "passive"))
      (node (ref "SENSOR2") (pin "1") (pinfunction "GND_1") (pintype "power_in"))
      (node (ref "SENSOR2") (pin "5") (pinfunction "SDO_5") (pintype "bidirectional"))
      (node (ref "SENSOR2") (pin "7") (pinfunction "GND_7") (pintype "power_in"))
      (node (ref "SJ1") (pin "1") (pinfunction "1_1") (pintype "passive"))
      (node (ref "TP4") (pin "TP") (pinfunction "TP_TP") (pintype "input"))
      (node (ref "TP5") (pin "TP") (pinfunction "TP_TP") (pintype "input"))
      (node (ref "U1") (pin "4") (pinfunction "GND_4") (pintype "power_in"))
      (node (ref "U1") (pin "9") (pinfunction "EXP_9") (pintype "passive"))
      (node (ref "U2") (pin "1") (pinfunction "GND_1") (pintype "power_in"))
      (node (ref "U2") (pin "28") (pinfunction "GND_28") (pintype "power_in"))
      (node (ref "U2") (pin "29_1") (pinfunction "GND_29_1") (pintype "power_in"))
      (node (ref "U2") (pin "29_2") (pinfunction "GND_29_2") (pintype "power_in"))
      (node (ref "U2") (pin "29_3") (pinfunction "GND_29_3") (pintype "power_in"))
      (node (ref "U2") (pin "29_4") (pinfunction "GND_29_4") (pintype "power_in"))
      (node (ref "U2") (pin "29_5") (pinfunction "GND_29_5") (pintype "power_in"))
      (node (ref "U2") (pin "29_6") (pinfunction "GND_29_6") (pintype "power_in"))
      (node (ref "U2") (pin "29_7") (pinfunction "GND_29_7") (pintype "power_in"))
      (node (ref "U2") (pin "29_8") (pinfunction "GND_29_8") (pintype "power_in"))
      (node (ref "U2") (pin "29_9") (pinfunction "GND_29_9") (pintype "power_in"))
      (node (ref "U3") (pin "13") (pinfunction "GND_13") (pintype "power_in"))
      (node (ref "U4") (pin "1") (pinfunction "CTG_1") (pintype "power_in"))
      (node (ref "U4") (pin "4") (pinfunction "GND_4") (pintype "power_in"))
      (node (ref "U4") (pin "6") (pinfunction "QSTRT_6") (pintype "input"))
      (node (ref "U4") (pin "9") (pinfunction "EP_9") (pintype "power_in"))
    )
    (net (code "14") (name "GPIO8") (class "Default")
      (node (ref "R1") (pin "1") (pinfunction "1_1") (pintype "passive"))
      (node (ref "U2") (pin "10") (pinfunction "IO8_10") (pintype "bidirectional"))
    )
    (net (code "15") (name "I2C_PW") (class "Default")
      (node (ref "C1") (pin "1") (pinfunction "1_1") (pintype "passive"))
      (node (ref "C2") (pin "1") (pinfunction "1_1") (pintype "passive"))
      (node (ref "R1_PINH") (pin "2") (pinfunction "2_2") (pintype "passive"))
      (node (ref "R2_PINH") (pin "2") (pinfunction "2_2") (pintype "passive"))
      (node (ref "SENSOR2") (pin "2") (pinfunction "CSB_2") (pintype "input"))
      (node (ref "SENSOR2") (pin "6") (pinfunction "VDDIO_6") (pintype "power_in"))
      (node (ref "SENSOR2") (pin "8") (pinfunction "VDD_8") (pintype "power_in"))
      (node (ref "U2") (pin "17") (pinfunction "IO19_17") (pintype "bidirectional"))
    )
    (net (code "16") (name "INT_RTC") (class "Default")
      (node (ref "R1_PINH1") (pin "1") (pinfunction "1_1") (pintype "passive"))
      (node (ref "TP15") (pin "TP") (pinfunction "TP_TP") (pintype "input"))
      (node (ref "U2") (pin "8") (pinfunction "IO0_8") (pintype "bidirectional"))
      (node (ref "U3") (pin "3") (pinfunction "SQW/~{INT}_3") (pintype "output"))
    )
    (net (code "17") (name "IO{slash}BOOT") (class "Default")
      (node (ref "BOOT_BUTTON") (pin "3") (pinfunction "3_3") (pintype "passive"))
      (node (ref "BOOT_BUTTON") (pin "4") (pinfunction "4_4") (pintype "passive"))
      (node (ref "C6") (pin "1") (pinfunction "1_1") (pintype "passive"))
      (node (ref "R_BOOT") (pin "2") (pinfunction "2_2") (pintype "passive"))
      (node (ref "U2") (pin "15") (pinfunction "IO9_15") (pintype "bidirectional"))
    )
    (net (code "18") (name "IO{slash}CHANGE") (class "Default")
      (node (ref "C10") (pin "1") (pinfunction "1_1") (pintype "passive"))
      (node (ref "CHANGE_BUTTON") (pin "3") (pinfunction "3_3") (pintype "passive"))
      (node (ref "CHANGE_BUTTON") (pin "4") (pinfunction "4_4") (pintype "passive"))
      (node (ref "R_CHANGE") (pin "2") (pinfunction "2_2") (pintype "passive"))
      (node (ref "U2") (pin "23") (pinfunction "IO15_23") (pintype "bidirectional"))
    )
    (net (code "19") (name "MISO") (class "Default")
      (node (ref "D12") (pin "2") (pinfunction "2_2") (pintype "passive"))
      (node (ref "J4") (pin "P7") (pinfunction "DAT0_P7") (pintype "bidirectional"))
      (node (ref "R8") (pin "1") (pinfunction "1_1") (pintype "passive"))
      (node (ref "TP6") (pin "TP") (pinfunction "TP_TP") (pintype "input"))
      (node (ref "U1") (pin "2") (pinfunction "DO(IO1)_2") (pintype "bidirectional"))
      (node (ref "U2") (pin "27") (pinfunction "IO2_27") (pintype "bidirectional"))
    )
    (net (code "20") (name "MOSI") (class "Default")
      (node (ref "D11") (pin "2") (pinfunction "2_2") (pintype "passive"))
      (node (ref "J1") (pin "14") (pinfunction "14_14") (pintype "bidirectional"))
      (node (ref "J4") (pin "P3") (pinfunction "CMD_P3") (pintype "bidirectional"))
      (node (ref "R7") (pin "1") (pinfunction "1_1") (pintype "passive"))
      (node (ref "TP7") (pin "TP") (pinfunction "TP_TP") (pintype "input"))
      (node (ref "U1") (pin "5") (pinfunction "DI(IO0)_5") (pintype "bidirectional"))
      (node (ref "U2") (pin "7") (pinfunction "IO7_7") (pintype "bidirectional"))
    )
    (net (code "21") (name "Net-(CHG_LED-PadC)") (class "Default")
      (node (ref "CHG_LED") (pin "C") (pinfunction "C_C") (pintype "passive"))
      (node (ref "R1_BAT") (pin "2") (pinfunction "2_2") (pintype "passive"))
    )
    (net (code "22") (name "Net-(D2-CATHODE)") (class "Default")
      (node (ref "C1_BAT1") (pin "1") (pinfunction "1_1") (pintype "passive"))
      (node (ref "D2") (pin "1") (pinfunction "CATHODE_1") (pintype "bidirectional"))
      (node (ref "IC4") (pin "1") (pinfunction "VIN_1") (pintype "bidirectional"))
      (node (ref "IC4") (pin "3") (pinfunction "CE_3") (pintype "bidirectional"))
      (node (ref "Q1") (pin "2") (pinfunction "S_2") (pintype "bidirectional"))
    )
    (net (code "23") (name "Net-(D3-A)") (class "Default")
      (node (ref "C4") (pin "1") (pinfunction "1_1") (pintype "passive"))
      (node (ref "D3") (pin "1") (pinfunction "A_1") (pintype "bidirectional"))
      (node (ref "D4") (pin "2") (pinfunction "K_2") (pintype "bidirectional"))
    )
    (net (code "24") (name "Net-(D7-CATHODE)") (class "Default")
      (node (ref "D7") (pin "1") (pinfunction "CATHODE_1") (pintype "bidirectional"))
      (node (ref "R_CAPACITOR") (pin "2") (pinfunction "2_2") (pintype "passive"))
    )
    (net (code "25") (name "Net-(EPD_C1-Pad1)") (class "Default")
      (node (ref "EPD_C1") (pin "1") (pinfunction "1_1") (pintype "passive"))
      (node (ref "J1") (pin "4") (pinfunction "4_4") (pintype "bidirectional"))
    )
    (net (code "26") (name "Net-(EPD_C2-Pad1)") (class "Default")
      (node (ref "EPD_C2") (pin "1") (pinfunction "1_1") (pintype "passive"))
      (node (ref "J1") (pin "5") (pinfunction "5_5") (pintype "bidirectional"))
    )
    (net (code "27") (name "Net-(EPD_C6-Pad1)") (class "Default")
      (node (ref "EPD_C6") (pin "1") (pinfunction "1_1") (pintype "passive"))
      (node (ref "J1") (pin "18") (pinfunction "18_18") (pintype "bidirectional"))
    )
    (net (code "28") (name "Net-(EPD_C7-Pad1)") (class "Default")
      (node (ref "EPD_C7") (pin "1") (pinfunction "1_1") (pintype "passive"))
      (node (ref "J1") (pin "19") (pinfunction "19_19") (pintype "bidirectional"))
    )
    (net (code "29") (name "Net-(EPD_C8-Pad1)") (class "Default")
      (node (ref "EPD_C8") (pin "1") (pinfunction "1_1") (pintype "passive"))
      (node (ref "J1") (pin "20") (pinfunction "20_20") (pintype "bidirectional"))
    )
    (net (code "30") (name "Net-(EPD_C10-Pad1)") (class "Default")
      (node (ref "EPD_C10") (pin "1") (pinfunction "1_1") (pintype "passive"))
      (node (ref "J1") (pin "22") (pinfunction "22_22") (pintype "bidirectional"))
    )
    (net (code "31") (name "Net-(EPD_C12-Pad1)") (class "Default")
      (node (ref "EPD_C12") (pin "1") (pinfunction "1_1") (pintype "passive"))
      (node (ref "J1") (pin "24") (pinfunction "24_24") (pintype "bidirectional"))
    )
    (net (code "32") (name "Net-(IC1-CT)") (class "Default")
      (node (ref "C_DELAY") (pin "1") (pinfunction "1_1") (pintype "passive"))
      (node (ref "IC1") (pin "5") (pinfunction "CT_5") (pintype "bidirectional"))
    )
    (net (code "33") (name "Net-(J2-PadA5)") (class "Default")
      (node (ref "J2") (pin "A5") (pinfunction "A5_A5") (pintype "bidirectional"))
      (node (ref "R2-USB1") (pin "2") (pinfunction "2_2") (pintype "passive"))
    )
    (net (code "34") (name "Net-(J2-PadB5)") (class "Default")
      (node (ref "J2") (pin "B5") (pinfunction "B5_B5") (pintype "bidirectional"))
      (node (ref "R2-USB") (pin "1") (pinfunction "1_1") (pintype "passive"))
    )
    (net (code "35") (name "Net-(MCP73831-PROG)") (class "Default")
      (node (ref "MCP73831") (pin "5") (pinfunction "PROG_5") (pintype "input"))
      (node (ref "R2_BAT") (pin "2") (pinfunction "2_2") (pintype "passive"))
    )
    (net (code "36") (name "Net-(MCP73831-STAT)") (class "Default")
      (node (ref "MCP73831") (pin "1") (pinfunction "STAT_1") (pintype "output"))
      (node (ref "R1_BAT") (pin "1") (pinfunction "1_1") (pintype "passive"))
    )
    (net (code "37") (name "PREVGH") (class "Default")
      (node (ref "D5") (pin "2") (pinfunction "K_2") (pintype "bidirectional"))
      (node (ref "EPD_C9") (pin "1") (pinfunction "1_1") (pintype "passive"))
      (node (ref "J1") (pin "21") (pinfunction "21_21") (pintype "bidirectional"))
    )
    (net (code "38") (name "PREVGL") (class "Default")
      (node (ref "D4") (pin "1") (pinfunction "A_1") (pintype "bidirectional"))
      (node (ref "EPD_C11") (pin "1") (pinfunction "1_1") (pintype "passive"))
      (node (ref "J1") (pin "23") (pinfunction "23_23") (pintype "bidirectional"))
    )
    (net (code "39") (name "RESE") (class "Default")
      (node (ref "J1") (pin "3") (pinfunction "3_3") (pintype "bidirectional"))
      (node (ref "Q3") (pin "2") (pinfunction "S_2") (pintype "bidirectional"))
      (node (ref "R4") (pin "1") (pinfunction "1_1") (pintype "passive"))
    )
    (net (code "40") (name "RESE'") (class "Default")
      (node (ref "R2") (pin "2") (pinfunction "2_2") (pintype "passive"))
      (node (ref "R4") (pin "2") (pinfunction "2_2") (pintype "passive"))
      (node (ref "SJ1") (pin "2") (pinfunction "2_2") (pintype "passive"))
    )
    (net (code "41") (name "RESET") (class "Default")
      (node (ref "C5") (pin "1") (pinfunction "1_1") (pintype "passive"))
      (node (ref "IC1") (pin "1") (pinfunction "VOUT_1") (pintype "bidirectional"))
      (node (ref "RESET_BUTTON") (pin "3") (pinfunction "3_3") (pintype "passive"))
      (node (ref "RESET_BUTTON") (pin "4") (pinfunction "4_4") (pintype "passive"))
      (node (ref "R_RESET") (pin "2") (pinfunction "2_2") (pintype "passive"))
      (node (ref "U2") (pin "3") (pinfunction "EN_3") (pintype "input"))
    )
    (net (code "42") (name "RTC_RST") (class "Default")
      (node (ref "U2") (pin "16") (pinfunction "IO18_16") (pintype "bidirectional"))
      (node (ref "U3") (pin "4") (pinfunction "~{RST}_4") (pintype "input"))
    )
    (net (code "43") (name "RX") (class "Default")
      (node (ref "TP2") (pin "TP") (pinfunction "TP_TP") (pintype "input"))
      (node (ref "U2") (pin "24") (pinfunction "RXD0/GPIO17_24") (pintype "bidirectional"))
    )
    (net (code "44") (name "SCK") (class "Default")
      (node (ref "D10") (pin "2") (pinfunction "2_2") (pintype "passive"))
      (node (ref "J1") (pin "13") (pinfunction "13_13") (pintype "bidirectional"))
      (node (ref "J4") (pin "P5") (pinfunction "CLK_P5") (pintype "bidirectional"))
      (node (ref "R6") (pin "1") (pinfunction "1_1") (pintype "passive"))
      (node (ref "TP8") (pin "TP") (pinfunction "TP_TP") (pintype "input"))
      (node (ref "U1") (pin "6") (pinfunction "CLK_6") (pintype "input"))
      (node (ref "U2") (pin "6") (pinfunction "IO6_6") (pintype "bidirectional"))
    )
    (net (code "45") (name "SCL") (class "Default")
      (node (ref "J3") (pin "4") (pinfunction "4_4") (pintype "passive"))
      (node (ref "R2_PINH") (pin "1") (pinfunction "1_1") (pintype "passive"))
      (node (ref "SENSOR2") (pin "4") (pinfunction "SCK_4") (pintype "input"))
      (node (ref "U2") (pin "20") (pinfunction "IO22_20") (pintype "bidirectional"))
      (node (ref "U3") (pin "16") (pinfunction "SCL_16") (pintype "input"))
      (node (ref "U4") (pin "7") (pinfunction "SCL_7") (pintype "input"))
    )
    (net (code "46") (name "SDA") (class "Default")
      (node (ref "J3") (pin "3") (pinfunction "3_3") (pintype "passive"))
      (node (ref "R1_PINH") (pin "1") (pinfunction "1_1") (pintype "passive"))
      (node (ref "SENSOR2") (pin "3") (pinfunction "SDI_3") (pintype "bidirectional"))
      (node (ref "U2") (pin "19") (pinfunction "IO21_19") (pintype "bidirectional"))
      (node (ref "U3") (pin "15") (pinfunction "SDA_15") (pintype "bidirectional"))
      (node (ref "U4") (pin "8") (pinfunction "SDA_8") (pintype "bidirectional"))
    )
    (net (code "47") (name "SRC") (class "Default")
      (node (ref "C4") (pin "2") (pinfunction "2_2") (pintype "passive"))
      (node (ref "D5") (pin "1") (pinfunction "A_1") (pintype "bidirectional"))
      (node (ref "L1") (pin "1") (pinfunction "1_1") (pintype "passive"))
      (node (ref "Q3") (pin "3") (pinfunction "D_3") (pintype "bidirectional"))
    )
    (net (code "48") (name "SS_SD") (class "Default")
      (node (ref "D8") (pin "2") (pinfunction "2_2") (pintype "passive"))
      (node (ref "J4") (pin "P2") (pinfunction "CD/DAT3_P2") (pintype "bidirectional"))
      (node (ref "R10") (pin "1") (pinfunction "1_1") (pintype "passive"))
      (node (ref "U2") (pin "4") (pinfunction "IO4_4") (pintype "bidirectional"))
    )
    (net (code "49") (name "TX") (class "Default")
      (node (ref "TP1") (pin "TP") (pinfunction "TP_TP") (pintype "input"))
      (node (ref "U2") (pin "25") (pinfunction "TXD0/GPIO16_25") (pintype "bidirectional"))
    )
    (net (code "50") (name "USB_D+") (class "Default")
      (node (ref "D1") (pin "1") (pinfunction "I/O1_1_1") (pintype "bidirectional"))
      (node (ref "U2") (pin "14") (pinfunction "IO13_14") (pintype "bidirectional"))
    )
    (net (code "51") (name "USB_D-") (class "Default")
      (node (ref "D1") (pin "3") (pinfunction "I/O2_1_3") (pintype "bidirectional"))
      (node (ref "U2") (pin "13") (pinfunction "IO12_13") (pintype "bidirectional"))
    )
    (net (code "52") (name "VBAT") (class "Default")
      (node (ref "C2_BAT") (pin "1") (pinfunction "1_1") (pintype "passive"))
      (node (ref "MCP73831") (pin "3") (pinfunction "VBAT_3") (pintype "power_in"))
      (node (ref "Q1") (pin "3") (pinfunction "D_3") (pintype "bidirectional"))
      (node (ref "TP3") (pin "TP") (pinfunction "TP_TP") (pintype "input"))
      (node (ref "U4") (pin "2") (pinfunction "CELL_2") (pintype "power_in"))
      (node (ref "U4") (pin "3") (pinfunction "VDD_3") (pintype "power_in"))
    )
    (net (code "53") (name "VBUS") (class "Default")
      (node (ref "C1_BAT") (pin "1") (pinfunction "1_1") (pintype "passive"))
      (node (ref "C4_USB") (pin "1") (pinfunction "1_1") (pintype "passive"))
      (node (ref "C5_USB") (pin "1") (pinfunction "1_1") (pintype "passive"))
      (node (ref "CHG_LED") (pin "A") (pinfunction "A_A") (pintype "passive"))
      (node (ref "D1") (pin "5") (pinfunction "VBUS_5") (pintype "bidirectional"))
      (node (ref "D2") (pin "2") (pinfunction "ANODE_2") (pintype "bidirectional"))
      (node (ref "MCP73831") (pin "4") (pinfunction "VIN_4") (pintype "power_in"))
      (node (ref "PFMP.050.1") (pin "2") (pinfunction "2_2") (pintype "passive"))
      (node (ref "Q1") (pin "1") (pinfunction "G_1") (pintype "bidirectional"))
      (node (ref "R1_PWRUSB") (pin "2") (pinfunction "2_2") (pintype "passive"))
      (node (ref "TP14") (pin "TP") (pinfunction "TP_TP") (pintype "input"))
    )
    (net (code "54") (name "VRTC") (class "Default")
      (node (ref "C10_SUPERCAP") (pin "2") (pinfunction "2_2") (pintype "passive"))
      (node (ref "C8") (pin "1") (pinfunction "1_1") (pintype "passive"))
      (node (ref "R_CAPACITOR") (pin "1") (pinfunction "1_1") (pintype "passive"))
      (node (ref "U3") (pin "14") (pinfunction "VBAT_14") (pintype "power_in"))
    )
    (net (code "55") (name "VUSB") (class "Default")
      (node (ref "J2") (pin "A4") (pinfunction "A4_A4") (pintype "bidirectional"))
      (node (ref "J2") (pin "A9") (pinfunction "A9_A9") (pintype "bidirectional"))
      (node (ref "J2") (pin "B4") (pinfunction "B4_B4") (pintype "bidirectional"))
      (node (ref "J2") (pin "B9") (pinfunction "B9_B9") (pintype "bidirectional"))
      (node (ref "PFMP.050.1") (pin "1") (pinfunction "1_1") (pintype "passive"))
    )
    (net (code "56") (name "unconnected-(IC1-NC-Pad4)") (class "Default")
      (node (ref "IC1") (pin "4") (pinfunction "NC_4") (pintype "no_connect"))
    )
    (net (code "57") (name "unconnected-(IC4-NC-Pad4)") (class "Default")
      (node (ref "IC4") (pin "4") (pinfunction "NC_4") (pintype "no_connect"))
    )
    (net (code "58") (name "unconnected-(J1-Pad1)") (class "Default")
      (node (ref "J1") (pin "1") (pinfunction "1_1") (pintype "bidirectional"))
    )
    (net (code "59") (name "unconnected-(J1-Pad6)") (class "Default")
      (node (ref "J1") (pin "6") (pinfunction "6_6") (pintype "bidirectional"))
    )
    (net (code "60") (name "unconnected-(J1-Pad7)") (class "Default")
      (node (ref "J1") (pin "7") (pinfunction "7_7") (pintype "bidirectional"))
    )
    (net (code "61") (name "unconnected-(J2-PadA8)") (class "Default")
      (node (ref "J2") (pin "A8") (pinfunction "A8_A8") (pintype "bidirectional"))
    )
    (net (code "62") (name "unconnected-(J2-PadB8)") (class "Default")
      (node (ref "J2") (pin "B8") (pinfunction "B8_B8") (pintype "bidirectional"))
    )
    (net (code "63") (name "unconnected-(J4-DAT1-PadP8)") (class "Default")
      (node (ref "J4") (pin "P8") (pinfunction "DAT1_P8") (pintype "bidirectional"))
    )
    (net (code "64") (name "unconnected-(J4-DAT2-PadP1)") (class "Default")
      (node (ref "J4") (pin "P1") (pinfunction "DAT2_P1") (pintype "bidirectional"))
    )
    (net (code "65") (name "unconnected-(J4-DETECTION_1-PadS1)") (class "Default")
      (node (ref "J4") (pin "S1") (pinfunction "DETECTION_1_S1") (pintype "bidirectional"))
    )
    (net (code "66") (name "unconnected-(J4-DETECTION_2-PadS2)") (class "Default")
      (node (ref "J4") (pin "S2") (pinfunction "DETECTION_2_S2") (pintype "bidirectional"))
    )
    (net (code "67") (name "unconnected-(U2-NC-Pad22)") (class "Default")
      (node (ref "U2") (pin "22") (pinfunction "NC_22") (pintype "no_connect"))
    )
    (net (code "68") (name "unconnected-(U4-~{ALERT}-Pad5)") (class "Default")
      (node (ref "U4") (pin "5") (pinfunction "~{ALERT}_5") (pintype "output"))
    )
  )
)
